# SeniorDesign.net
KiCad netlist of a schematic drawn in EasyEDA
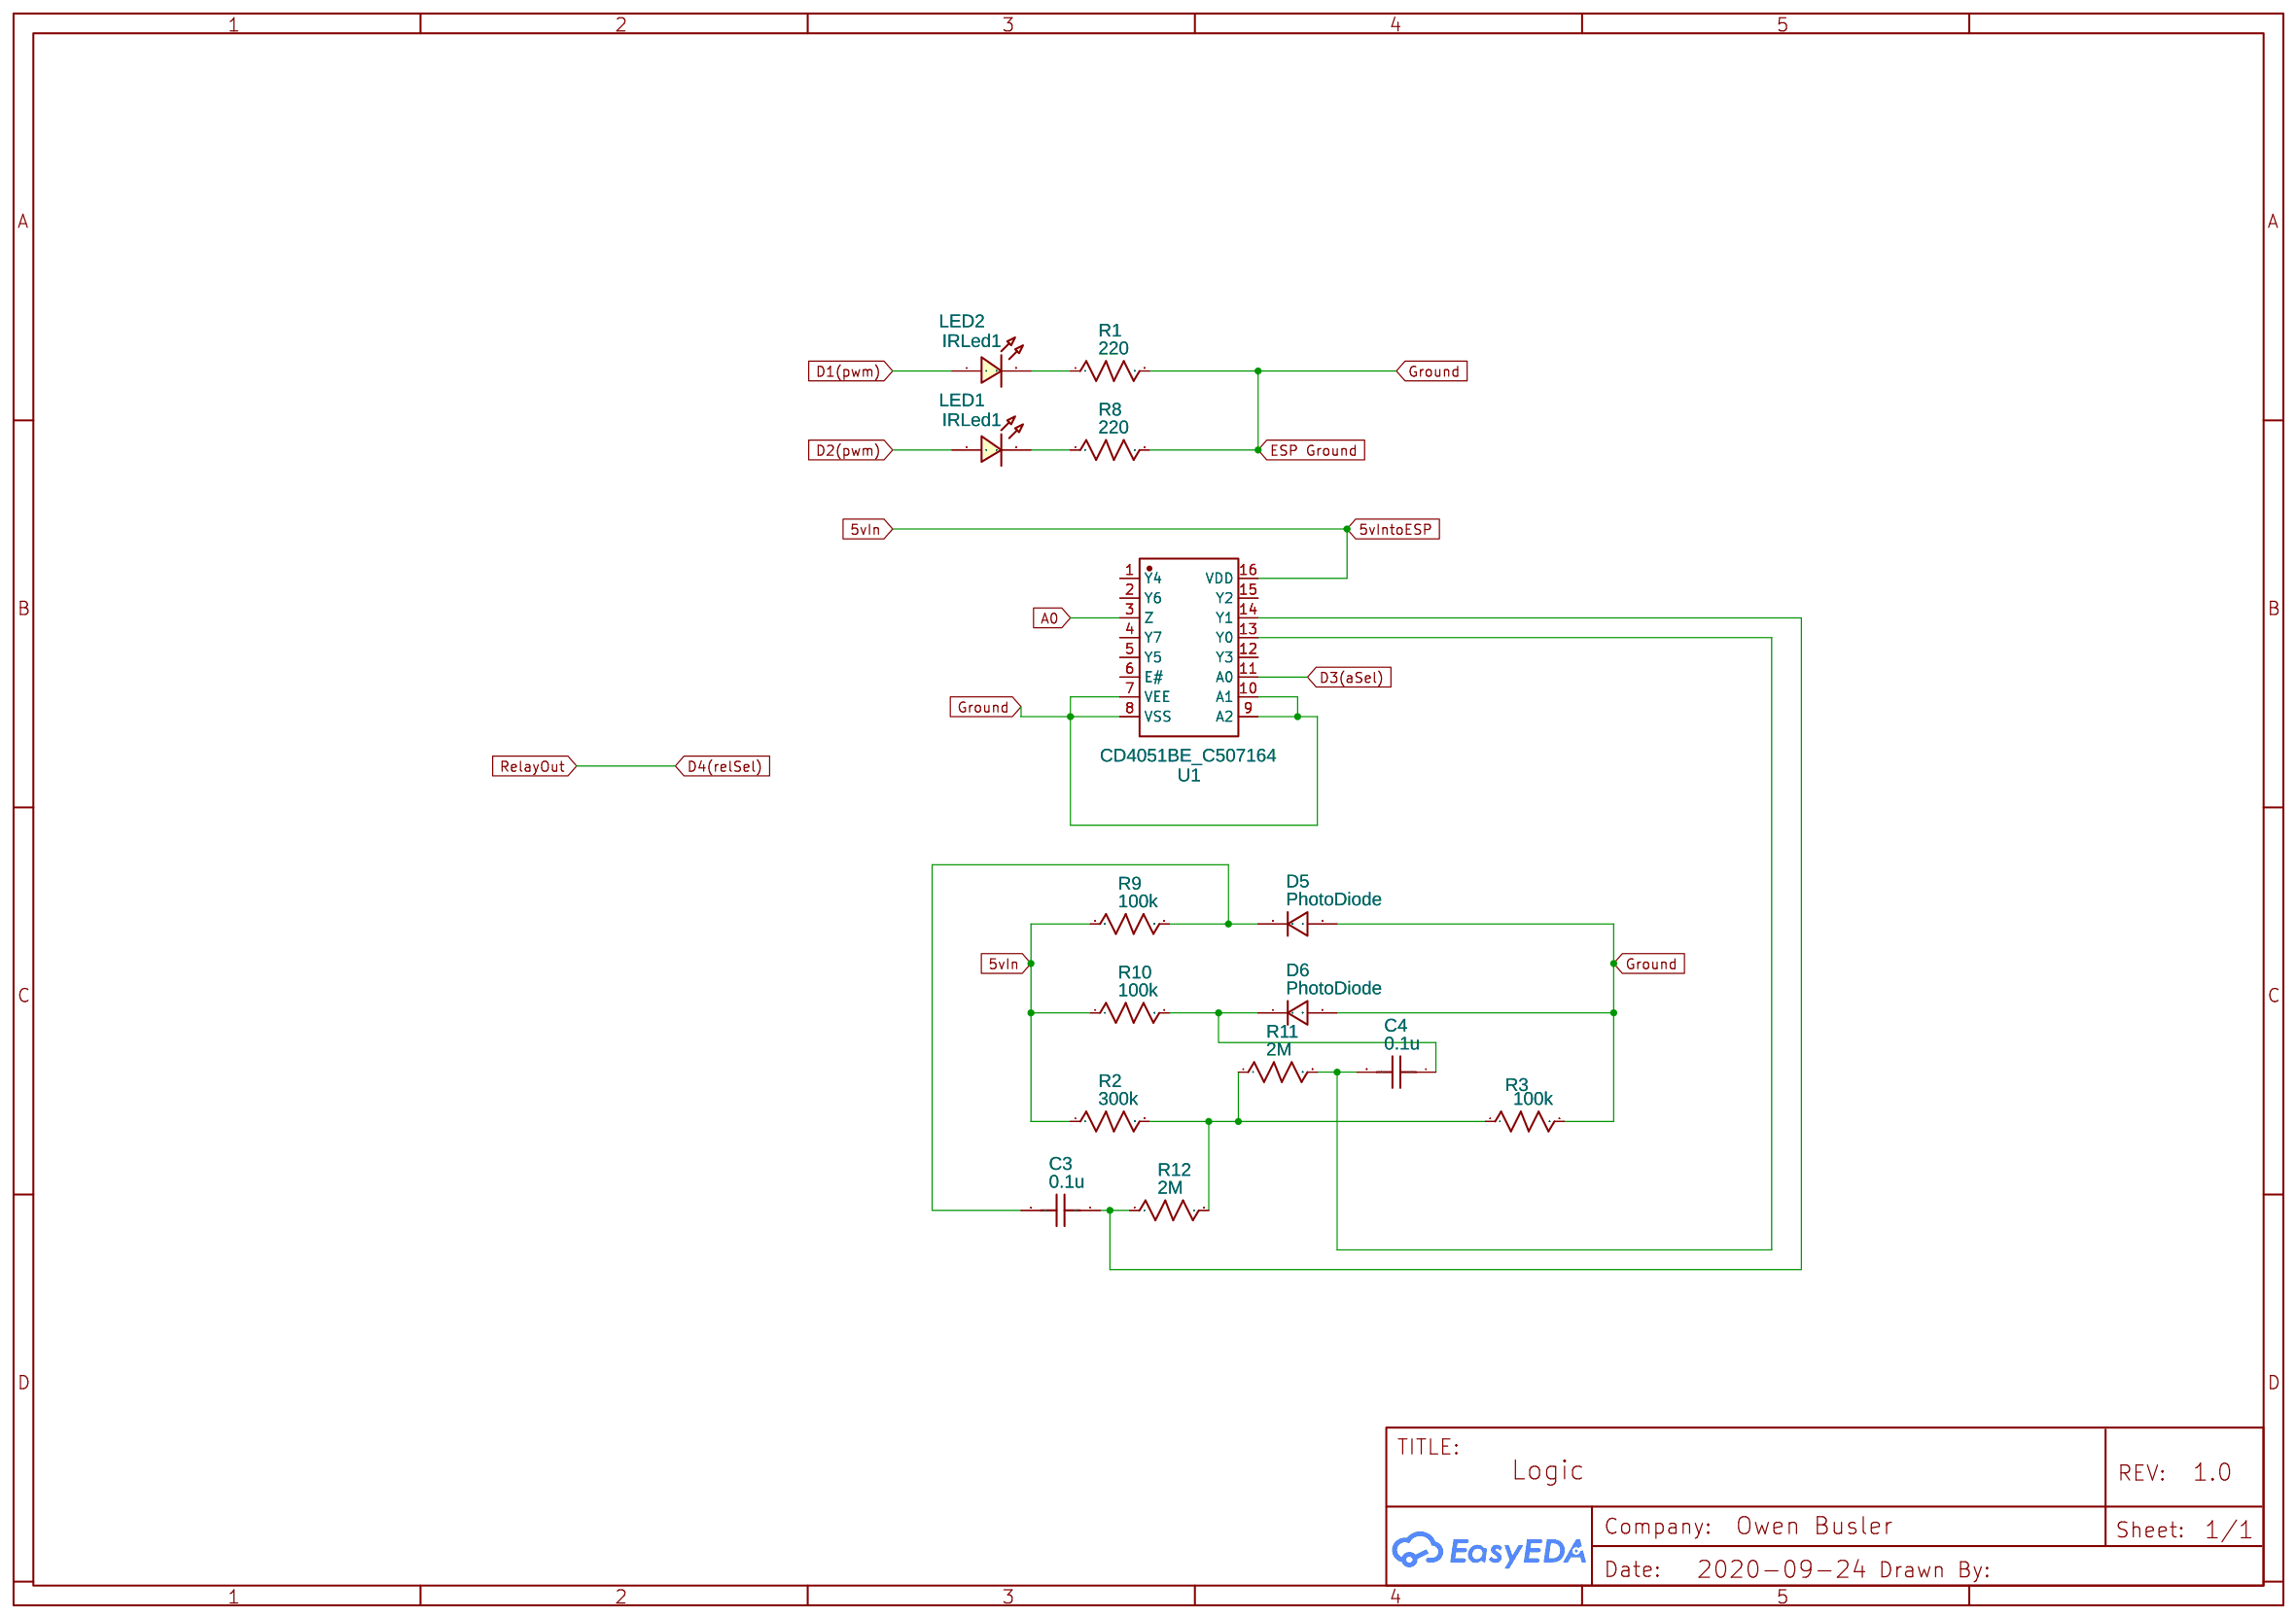
[diagram p0: LogicSch]
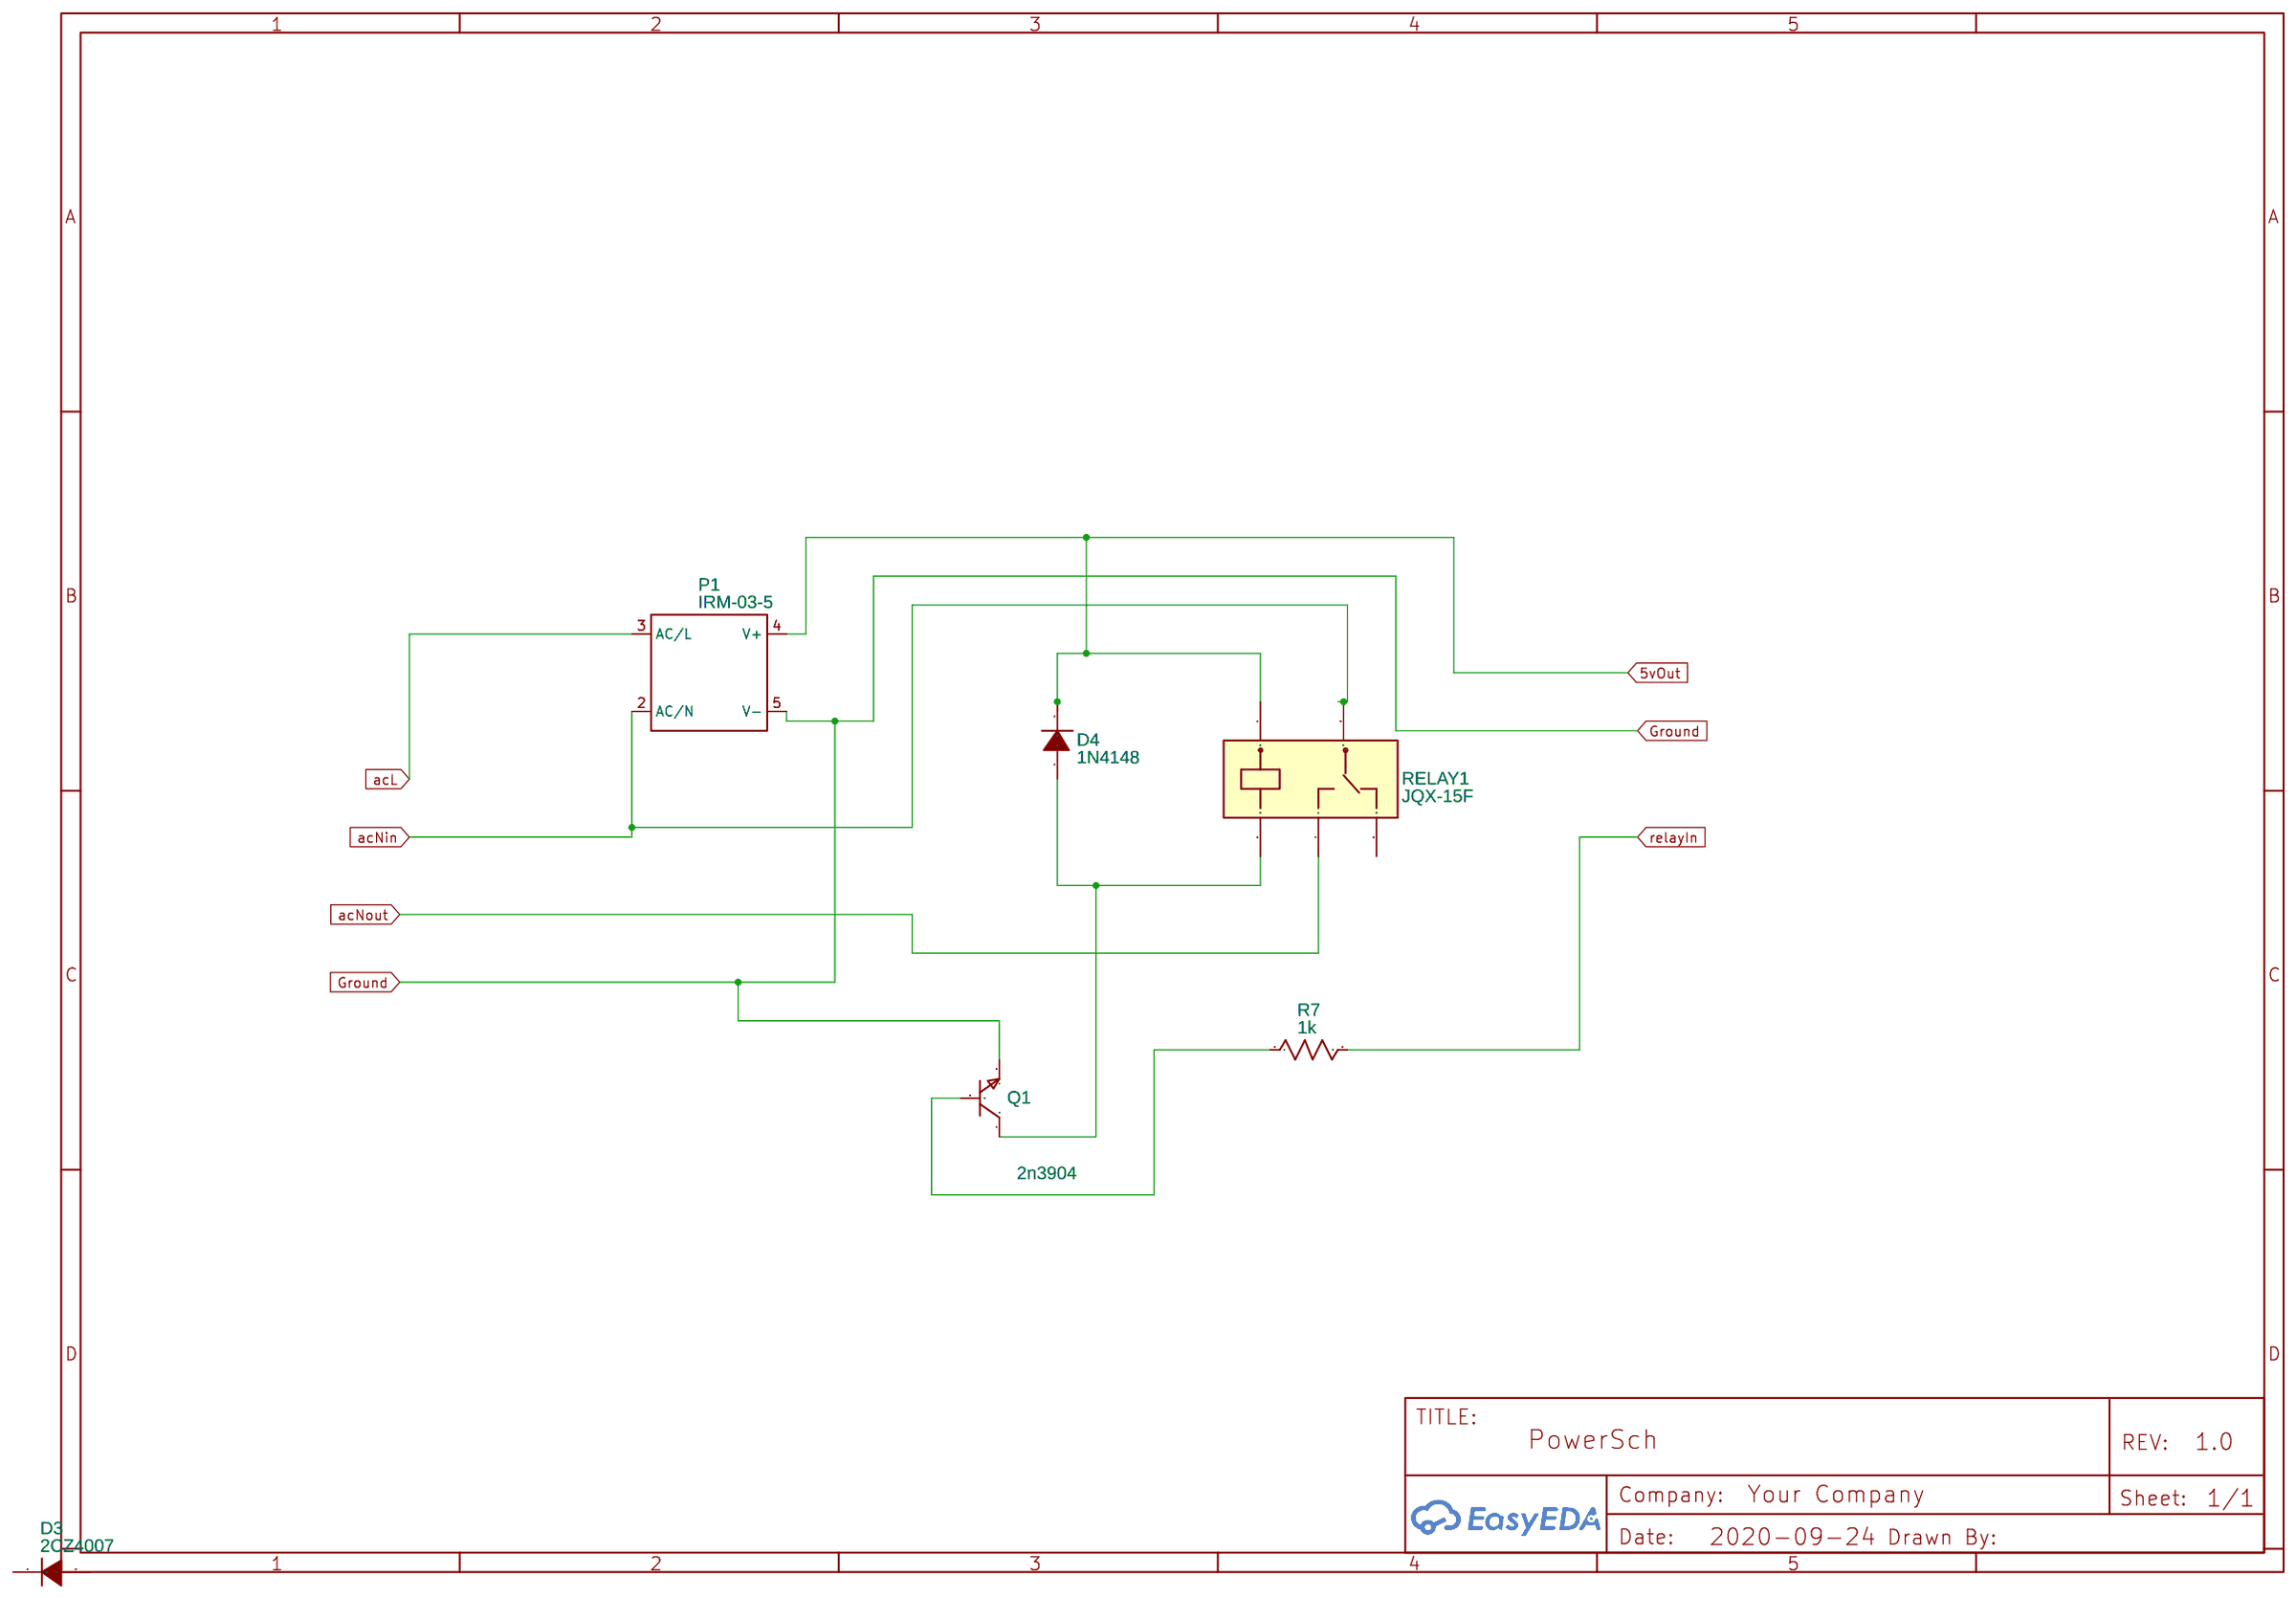
[diagram p1: PowerSch]

(export (version "E")
  (design (tool "Eeschema 10.0.6"))
  (components
    (comp (ref "C3") (value "0.1u") (libsource (lib "") (part "C_0603_US")))
    (comp (ref "C4") (value "0.1u") (libsource (lib "") (part "C_0603_US")))
    (comp (ref "D5")
      (value "PhotoDiode")
      (fields (field (name "BOM_Manufacturer Part") "1N4007W") (field (name "BOM_Supplier Part") "C328592"))
      (libsource (lib "") (part "1N4007W"))
    )
    (comp (ref "D6")
      (value "PhotoDiode")
      (fields (field (name "BOM_Manufacturer Part") "1N4007W") (field (name "BOM_Supplier Part") "C328592"))
      (libsource (lib "") (part "1N4007W"))
    )
    (comp (ref "LED1")
      (value "IRLed1")
      (fields
        (field (name "BOM_Manufacturer Part") "19-217/R6C-AL1M2VY/3T")
        (field (name "BOM_Supplier Part") "C72044")
      )
      (libsource (lib "") (part "LED-0603_R"))
    )
    (comp (ref "LED2")
      (value "IRLed1")
      (fields
        (field (name "BOM_Manufacturer Part") "19-217/R6C-AL1M2VY/3T")
        (field (name "BOM_Supplier Part") "C72044")
      )
      (libsource (lib "") (part "LED-0603_R"))
    )
    (comp (ref "R1") (value "220") (libsource (lib "") (part "R_0603_US")))
    (comp (ref "R2") (value "300k") (libsource (lib "") (part "R_0603_US")))
    (comp (ref "R3") (value "100k") (libsource (lib "") (part "R_0603_US")))
    (comp (ref "R8") (value "220") (libsource (lib "") (part "R_0603_US")))
    (comp (ref "R9") (value "100k") (libsource (lib "") (part "R_0603_US")))
    (comp (ref "R10") (value "100k") (libsource (lib "") (part "R_0603_US")))
    (comp (ref "R11") (value "2M") (libsource (lib "") (part "R_0603_US")))
    (comp (ref "R12") (value "2M") (libsource (lib "") (part "R_0603_US")))
    (comp (ref "U1")
      (value "CD4051BE_C507164")
      (fields (field (name "BOM_Manufacturer Part") "CD4051BE") (field (name "BOM_Supplier Part") "C507164"))
      (libsource (lib "") (part "CD4051BE_C507164"))
    )
    (comp (ref "D3")
      (value "2CZ4007")
      (fields (field (name "BOM_Supplier Part") "C85712"))
      (libsource (lib "") (part "2CZ4007"))
    )
    (comp (ref "D4")
      (value "1N4148")
      (fields (field (name "BOM_Supplier Part") "C14516"))
      (libsource (lib "") (part "1N4148"))
    )
    (comp (ref "P1") (value "IRM-03-5") (libsource (lib "") (part "IRM-03-5")))
    (comp (ref "Q1") (value "2n3904") (libsource (lib "") (part "2n3904")))
    (comp (ref "R7") (value "1k") (libsource (lib "") (part "R_0603_US")))
    (comp (ref "RELAY1")
      (value "JQX-15F")
      (fields
        (field (name "BOM_Manufacturer Part") "JQX-105F-1/012D-1HS")
        (field (name "BOM_Supplier Part") "C3631")
      )
      (libsource (lib "") (part "JQX-15F"))
    )
  )
  (nets
    (net (code "1") (name "5vIn") (class "Default")
      (node (ref "R10") (pin "1") (pinfunction "1_1") (pintype "unspecified"))
      (node (ref "R2") (pin "1") (pinfunction "1_1") (pintype "unspecified"))
      (node (ref "R9") (pin "1") (pinfunction "1_1") (pintype "unspecified"))
      (node (ref "U1") (pin "16") (pinfunction "VDD_16") (pintype "unspecified"))
    )
    (net (code "2") (name "5vOut") (class "Default")
      (node (ref "D4") (pin "2") (pinfunction "C_2") (pintype "unspecified"))
      (node (ref "P1") (pin "4") (pinfunction "V+_4") (pintype "bidirectional"))
      (node (ref "RELAY1") (pin "1") (pinfunction "1_1") (pintype "input"))
    )
    (net (code "3") (name "A0") (class "Default")
      (node (ref "U1") (pin "3") (pinfunction "Z_3") (pintype "unspecified"))
    )
    (net (code "4") (name "D1(pwm)") (class "Default")
      (node (ref "LED2") (pin "1") (pinfunction "1_1") (pintype "unspecified"))
    )
    (net (code "5") (name "D2(pwm)") (class "Default")
      (node (ref "LED1") (pin "1") (pinfunction "1_1") (pintype "unspecified"))
    )
    (net (code "6") (name "D3(aSel)") (class "Default")
      (node (ref "U1") (pin "11") (pinfunction "A0_11") (pintype "unspecified"))
    )
    (net (code "8") (name "ESP Ground") (class "Default")
      (node (ref "D5") (pin "2") (pinfunction "2_2") (pintype "unspecified"))
      (node (ref "D6") (pin "2") (pinfunction "2_2") (pintype "unspecified"))
      (node (ref "P1") (pin "5") (pinfunction "V-_5") (pintype "bidirectional"))
      (node (ref "Q1") (pin "3") (pinfunction "E_3") (pintype "unspecified"))
      (node (ref "R1") (pin "2") (pinfunction "2_2") (pintype "unspecified"))
      (node (ref "R3") (pin "2") (pinfunction "2_2") (pintype "unspecified"))
      (node (ref "R8") (pin "2") (pinfunction "2_2") (pintype "unspecified"))
      (node (ref "U1") (pin "10") (pinfunction "A1_10") (pintype "unspecified"))
      (node (ref "U1") (pin "7") (pinfunction "VEE_7") (pintype "unspecified"))
      (node (ref "U1") (pin "8") (pinfunction "VSS_8") (pintype "unspecified"))
      (node (ref "U1") (pin "9") (pinfunction "A2_9") (pintype "unspecified"))
    )
    (net (code "9") (name "Net-(C3-Pad2)") (class "Default")
      (node (ref "C3") (pin "2") (pinfunction "2_2") (pintype "unspecified"))
      (node (ref "D5") (pin "1") (pinfunction "1_1") (pintype "unspecified"))
      (node (ref "R9") (pin "2") (pinfunction "2_2") (pintype "unspecified"))
    )
    (net (code "10") (name "Net-(C4-Pad1)") (class "Default")
      (node (ref "C4") (pin "1") (pinfunction "1_1") (pintype "unspecified"))
      (node (ref "D6") (pin "1") (pinfunction "1_1") (pintype "unspecified"))
      (node (ref "R10") (pin "2") (pinfunction "2_2") (pintype "unspecified"))
    )
    (net (code "11") (name "Net-(D4-A)") (class "Default")
      (node (ref "D4") (pin "1") (pinfunction "A_1") (pintype "unspecified"))
      (node (ref "Q1") (pin "1") (pinfunction "C_1") (pintype "unspecified"))
      (node (ref "RELAY1") (pin "2") (pinfunction "2_2") (pintype "input"))
    )
    (net (code "12") (name "Net-(LED1-Pad2)") (class "Default")
      (node (ref "LED1") (pin "2") (pinfunction "2_2") (pintype "unspecified"))
      (node (ref "R8") (pin "1") (pinfunction "1_1") (pintype "unspecified"))
    )
    (net (code "13") (name "Net-(LED2-Pad2)") (class "Default")
      (node (ref "LED2") (pin "2") (pinfunction "2_2") (pintype "unspecified"))
      (node (ref "R1") (pin "1") (pinfunction "1_1") (pintype "unspecified"))
    )
    (net (code "14") (name "Net-(Q1-B)") (class "Default")
      (node (ref "Q1") (pin "2") (pinfunction "B_2") (pintype "unspecified"))
      (node (ref "R7") (pin "1") (pinfunction "1_1") (pintype "unspecified"))
    )
    (net (code "15") (name "Net-(R11-Pad1)") (class "Default")
      (node (ref "R11") (pin "1") (pinfunction "1_1") (pintype "unspecified"))
      (node (ref "R12") (pin "2") (pinfunction "2_2") (pintype "unspecified"))
      (node (ref "R2") (pin "2") (pinfunction "2_2") (pintype "unspecified"))
      (node (ref "R3") (pin "1") (pinfunction "1_1") (pintype "unspecified"))
    )
    (net (code "16") (name "Net-(U1-Y0)") (class "Default")
      (node (ref "C4") (pin "2") (pinfunction "2_2") (pintype "unspecified"))
      (node (ref "R11") (pin "2") (pinfunction "2_2") (pintype "unspecified"))
      (node (ref "U1") (pin "13") (pinfunction "Y0_13") (pintype "unspecified"))
    )
    (net (code "17") (name "Net-(U1-Y1)") (class "Default")
      (node (ref "C3") (pin "1") (pinfunction "1_1") (pintype "unspecified"))
      (node (ref "R12") (pin "1") (pinfunction "1_1") (pintype "unspecified"))
      (node (ref "U1") (pin "14") (pinfunction "Y1_14") (pintype "unspecified"))
    )
    (net (code "18") (name "acL") (class "Default")
      (node (ref "P1") (pin "3") (pinfunction "AC/L_3") (pintype "bidirectional"))
    )
    (net (code "19") (name "acNin") (class "Default")
      (node (ref "P1") (pin "2") (pinfunction "AC/N_2") (pintype "bidirectional"))
      (node (ref "RELAY1") (pin "5") (pinfunction "5_5") (pintype "unspecified"))
    )
    (net (code "20") (name "acNout") (class "Default")
      (node (ref "RELAY1") (pin "4") (pinfunction "4_4") (pintype "input"))
    )
    (net (code "21") (name "relayIn") (class "Default")
      (node (ref "R7") (pin "2") (pinfunction "2_2") (pintype "unspecified"))
    )
    (net (code "22") (name "unconnected-(D3-A-Pad2)") (class "Default")
      (node (ref "D3") (pin "2") (pinfunction "A_2") (pintype "unspecified"))
    )
    (net (code "23") (name "unconnected-(D3-C-Pad1)") (class "Default")
      (node (ref "D3") (pin "1") (pinfunction "C_1") (pintype "unspecified"))
    )
    (net (code "24") (name "unconnected-(RELAY1-Pad3)") (class "Default")
      (node (ref "RELAY1") (pin "3") (pinfunction "3_3") (pintype "input"))
    )
    (net (code "25") (name "unconnected-(U1-E#-Pad6)") (class "Default")
      (node (ref "U1") (pin "6") (pinfunction "E#_6") (pintype "unspecified"))
    )
    (net (code "26") (name "unconnected-(U1-Y2-Pad15)") (class "Default")
      (node (ref "U1") (pin "15") (pinfunction "Y2_15") (pintype "unspecified"))
    )
    (net (code "27") (name "unconnected-(U1-Y3-Pad12)") (class "Default")
      (node (ref "U1") (pin "12") (pinfunction "Y3_12") (pintype "unspecified"))
    )
    (net (code "28") (name "unconnected-(U1-Y4-Pad1)") (class "Default")
      (node (ref "U1") (pin "1") (pinfunction "Y4_1") (pintype "unspecified"))
    )
    (net (code "29") (name "unconnected-(U1-Y5-Pad5)") (class "Default")
      (node (ref "U1") (pin "5") (pinfunction "Y5_5") (pintype "unspecified"))
    )
    (net (code "30") (name "unconnected-(U1-Y6-Pad2)") (class "Default")
      (node (ref "U1") (pin "2") (pinfunction "Y6_2") (pintype "unspecified"))
    )
    (net (code "31") (name "unconnected-(U1-Y7-Pad4)") (class "Default")
      (node (ref "U1") (pin "4") (pinfunction "Y7_4") (pintype "unspecified"))
    )
  )
)
